# Supply.net
KiCad netlist of a schematic drawn in Altium Designer
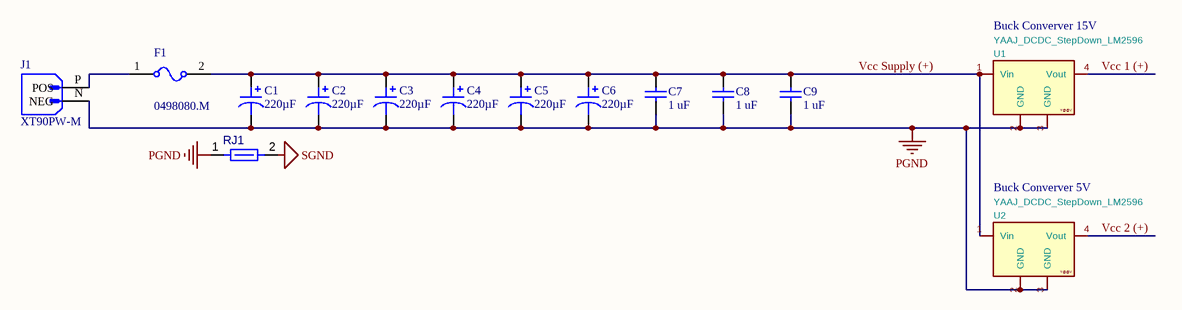
[diagram p0: Supply.SchDoc]

(export (version "E")
  (design (tool "Eeschema 10.0.6"))
  (components
    (comp (ref "C1")
      (value "220µF")
      (footprint "CAP TH ALUM ELEC D10.00mm S5.00mm H20.00mm")
      (description "CAP ALUM 220UF 20% 63V RADIAL")
      (fields (field (name "PART NUMBER") "UPW1J221MPD") (field (name "MANUFACTURER") "Nichicon"))
      (libsource (lib "Celestial Altium Library - altium_library") (part "Polarised Capacitor"))
    )
    (comp (ref "C2")
      (value "220µF")
      (footprint "CAP TH ALUM ELEC D10.00mm S5.00mm H20.00mm")
      (description "UPW1J221MPD\r\nCAP ALUM 220UF 20% 63V RADIAL")
      (fields (field (name "PART NUMBER") "UPW1J221MPD") (field (name "MANUFACTURER") "Nichicon"))
      (libsource (lib "Celestial Altium Library - altium_library") (part "Polarised Capacitor"))
    )
    (comp (ref "C3")
      (value "220µF")
      (footprint "CAP TH ALUM ELEC D10.00mm S5.00mm H20.00mm")
      (description "CAP ALUM 220UF 20% 63V RADIAL")
      (fields (field (name "PART NUMBER") "UPW1J221MPD") (field (name "MANUFACTURER") "Nichicon"))
      (libsource (lib "Celestial Altium Library - altium_library") (part "Polarised Capacitor"))
    )
    (comp (ref "C4")
      (value "220µF")
      (footprint "CAP TH ALUM ELEC D10.00mm S5.00mm H20.00mm")
      (description "CAP ALUM 220UF 20% 63V RADIAL")
      (fields (field (name "PART NUMBER") "UPW1J221MPD") (field (name "MANUFACTURER") "Nichicon"))
      (libsource (lib "Celestial Altium Library - altium_library") (part "Polarised Capacitor"))
    )
    (comp (ref "C5")
      (value "220µF")
      (footprint "CAP TH ALUM ELEC D10.00mm S5.00mm H20.00mm")
      (description "CAP ALUM 220UF 20% 63V RADIAL")
      (fields (field (name "PART NUMBER") "UPW1J221MPD") (field (name "MANUFACTURER") "Nichicon"))
      (libsource (lib "Celestial Altium Library - altium_library") (part "Polarised Capacitor"))
    )
    (comp (ref "C6")
      (value "220µF")
      (footprint "CAP TH ALUM ELEC D10.00mm S5.00mm H20.00mm")
      (description "CAP ALUM 220UF 20% 63V RADIAL")
      (fields (field (name "PART NUMBER") "UPW1J221MPD") (field (name "MANUFACTURER") "Nichicon"))
      (libsource (lib "Celestial Altium Library - altium_library") (part "Polarised Capacitor"))
    )
    (comp (ref "C7")
      (value "1 uF")
      (footprint "CAPR51-254-508X318X736")
      (libsource (lib "Altium Content Vault") (part "CAP-NP-2"))
    )
    (comp (ref "C8")
      (value "1 uF")
      (footprint "CAPR51-254-508X318X736")
      (libsource (lib "Altium Content Vault") (part "CAP-NP-2"))
    )
    (comp (ref "C9")
      (value "1 uF")
      (footprint "CAPR51-254-508X318X736")
      (libsource (lib "Altium Content Vault") (part "CAP-NP-2"))
    )
    (comp (ref "F1")
      (value "0498080.M")
      (footprint "0498080M")
      (description "80 A 32 V Fuse Automotive Bolt Mount Auto Link")
      (libsource (lib "Schlib") (part "Fuse"))
    )
    (comp (ref "J1")
      (value "XT90PW-M")
      (footprint "AMASS_XT90PW-M")
      (description "Socket; DC supply; XT90; male; PIN: 2; on PCBs; THT; Colour: yellow")
      (fields (field (name "MF") "AMASS"))
      (libsource (lib "XT90PW-M") (part "XT90PW-M"))
    )
    (comp (ref "RJ1")
      (value "Net Tie 0.6x1.4mm")
      (footprint "SHORT10_8MIL-FP")
      (libsource (lib "Pessoal") (part "CMP-00022-00002-2"))
    )
    (comp (ref "U1")
      (value "Buck Converver 15V")
      (footprint "YAAJ_DCDC_StepDown_LM2596")
      (fields (field (name "ALTIUM_VALUE") "YAAJ_DCDC_StepDown_LM2596"))
      (libsource (lib "DCDC_StepDown_LM2596") (part "YAAJ_DCDC_StepDown_LM2596"))
    )
    (comp (ref "U2")
      (value "Buck Converver 5V")
      (footprint "YAAJ_DCDC_StepDown_LM2596")
      (fields (field (name "ALTIUM_VALUE") "YAAJ_DCDC_StepDown_LM2596"))
      (libsource (lib "DCDC_StepDown_LM2596") (part "YAAJ_DCDC_StepDown_LM2596"))
    )
  )
  (nets
    (net (code "1") (name "/Vcc 1 (+)") (class "Default")
      (node (ref "U1") (pin "4") (pinfunction "Vout_4") (pintype "passive"))
    )
    (net (code "2") (name "/Vcc 2 (+)") (class "Default")
      (node (ref "U2") (pin "4") (pinfunction "Vout_4") (pintype "passive"))
    )
    (net (code "3") (name "/Vcc Supply (+)") (class "Default")
      (node (ref "C1") (pin "1") (pinfunction "1_1") (pintype "passive"))
      (node (ref "C2") (pin "1") (pinfunction "1_1") (pintype "passive"))
      (node (ref "C3") (pin "1") (pinfunction "1_1") (pintype "passive"))
      (node (ref "C4") (pin "1") (pinfunction "1_1") (pintype "passive"))
      (node (ref "C5") (pin "1") (pinfunction "1_1") (pintype "passive"))
      (node (ref "C6") (pin "1") (pinfunction "1_1") (pintype "passive"))
      (node (ref "C7") (pin "2") (pinfunction "2_2") (pintype "passive"))
      (node (ref "C8") (pin "2") (pinfunction "2_2") (pintype "passive"))
      (node (ref "C9") (pin "2") (pinfunction "2_2") (pintype "passive"))
      (node (ref "F1") (pin "2") (pinfunction "2_2") (pintype "passive"))
      (node (ref "U1") (pin "1") (pinfunction "Vin_1") (pintype "passive"))
      (node (ref "U2") (pin "1") (pinfunction "Vin_1") (pintype "passive"))
    )
    (net (code "4") (name "Net-(J1-POS)") (class "Default")
      (node (ref "F1") (pin "1") (pinfunction "1_1") (pintype "passive"))
      (node (ref "J1") (pin "P") (pinfunction "POS_P") (pintype "passive"))
    )
    (net (code "5") (name "PGND") (class "Default")
      (node (ref "C1") (pin "2") (pinfunction "2_2") (pintype "passive"))
      (node (ref "C2") (pin "2") (pinfunction "2_2") (pintype "passive"))
      (node (ref "C3") (pin "2") (pinfunction "2_2") (pintype "passive"))
      (node (ref "C4") (pin "2") (pinfunction "2_2") (pintype "passive"))
      (node (ref "C5") (pin "2") (pinfunction "2_2") (pintype "passive"))
      (node (ref "C6") (pin "2") (pinfunction "2_2") (pintype "passive"))
      (node (ref "C7") (pin "1") (pinfunction "1_1") (pintype "passive"))
      (node (ref "C8") (pin "1") (pinfunction "1_1") (pintype "passive"))
      (node (ref "C9") (pin "1") (pinfunction "1_1") (pintype "passive"))
      (node (ref "J1") (pin "N") (pinfunction "NEG_N") (pintype "passive"))
      (node (ref "RJ1") (pin "1") (pinfunction "1_1") (pintype "passive"))
      (node (ref "U1") (pin "2") (pinfunction "GND_2") (pintype "passive"))
      (node (ref "U1") (pin "3") (pinfunction "GND_3") (pintype "passive"))
      (node (ref "U2") (pin "2") (pinfunction "GND_2") (pintype "passive"))
      (node (ref "U2") (pin "3") (pinfunction "GND_3") (pintype "passive"))
    )
    (net (code "6") (name "SGND") (class "Default")
      (node (ref "RJ1") (pin "2") (pinfunction "2_2") (pintype "passive"))
    )
  )
)
